# HBridges.net
KiCad netlist of a schematic drawn in Altium Designer
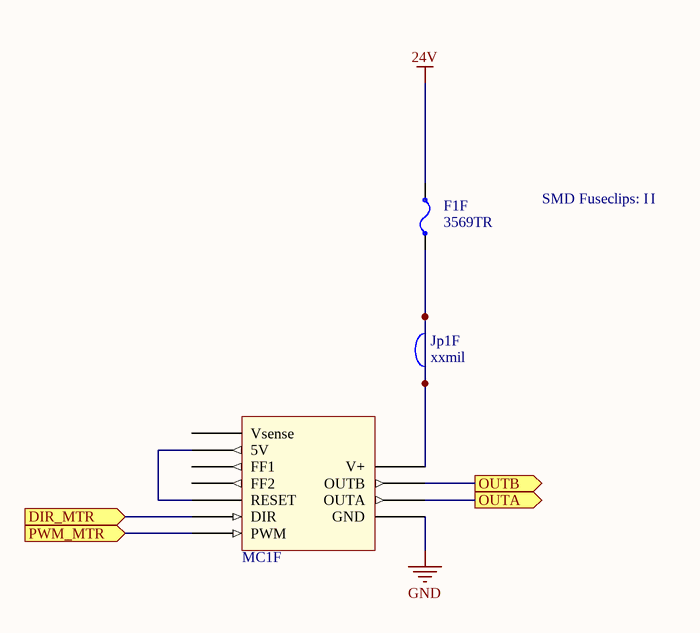
[diagram p0: HBridges.SchDoc]

(export (version "E")
  (design (tool "Eeschema 10.0.6"))
  (components
    (comp (ref "F1F")
      (value "3569TR")
      (footprint "Horizontal SMD fuse clip")
      (description "Fuse Clip Assembly")
      (fields (field (name "MANUFACTURER PART NUMBER") "3569TR"))
      (libsource (lib "Keystone SchLib") (part "3569TR"))
    )
    (comp (ref "i10F")
      (value "3569TR (Placeholder)")
      (description "Fuse Clip")
      (fields (field (name "MANUFACTURER PART NUMBER") "3569TR"))
      (libsource (lib "Keystone SchLib") (part "3569TR (Placeholder)"))
    )
    (comp (ref "i11F")
      (value "3569TR (Placeholder)")
      (description "Fuse Clip")
      (fields (field (name "MANUFACTURER PART NUMBER") "3569TR"))
      (libsource (lib "") (part "3569TR (Placeholder)_1"))
    )
    (comp (ref "Jp1F")
      (value "xxmil")
      (footprint "Jumper, 12AWG, 0.6\"")
      (description "Resistor")
      (fields (field (name "Comment") "Jumper"))
      (libsource (lib "URC") (part "Jump"))
    )
    (comp (ref "MC1F")
      (value "Motor Controller")
      (footprint "Pololu 24v12")
      (description "Pololu 24v12 Motor Driver")
      (libsource (lib "URC_Lib") (part "Pololu 24v12"))
    )
  )
  (nets
    (net (code "1") (name "/DIR_MTR") (class "Default")
      (node (ref "MC1F") (pin "DIR") (pinfunction "DIR_DIR") (pintype "input"))
    )
    (net (code "2") (name "/OUTA") (class "Default")
      (node (ref "MC1F") (pin "OUTA") (pinfunction "OUTA_OUTA") (pintype "output"))
    )
    (net (code "3") (name "/OUTB") (class "Default")
      (node (ref "MC1F") (pin "OUTB") (pinfunction "OUTB_OUTB") (pintype "output"))
    )
    (net (code "4") (name "/PWM_MTR") (class "Default")
      (node (ref "MC1F") (pin "PWM") (pinfunction "PWM_PWM") (pintype "input"))
    )
    (net (code "5") (name "24V") (class "Default")
      (node (ref "F1F") (pin "1") (pinfunction "1_1") (pintype "passive"))
    )
    (net (code "6") (name "GND") (class "Default")
      (node (ref "MC1F") (pin "GND") (pinfunction "GND_GND") (pintype "power_in"))
    )
    (net (code "7") (name "Net-(F1F-Pad2)") (class "Default")
      (node (ref "F1F") (pin "2") (pinfunction "2_2") (pintype "passive"))
      (node (ref "Jp1F") (pin "1") (pinfunction "1_1") (pintype "passive"))
      (node (ref "Jp1F") (pin "2") (pinfunction "2_2") (pintype "passive"))
      (node (ref "MC1F") (pin "V+") (pinfunction "V+_V+") (pintype "power_in"))
    )
    (net (code "8") (name "Net-(MC1F-Pad5V)") (class "Default")
      (node (ref "MC1F") (pin "5V") (pinfunction "5V_5V") (pintype "output"))
      (node (ref "MC1F") (pin "RESET") (pinfunction "RESET_RESET") (pintype "passive"))
    )
    (net (code "9") (name "unconnected-(MC1F-PadFF1)") (class "Default")
      (node (ref "MC1F") (pin "FF1") (pinfunction "FF1_FF1") (pintype "output"))
    )
    (net (code "10") (name "unconnected-(MC1F-PadFF2)") (class "Default")
      (node (ref "MC1F") (pin "FF2") (pinfunction "FF2_FF2") (pintype "output"))
    )
    (net (code "11") (name "unconnected-(MC1F-Vsense-PadV+_SENSE)") (class "Default")
      (node (ref "MC1F") (pin "V+_SENSE") (pinfunction "Vsense_V+_SENSE") (pintype "passive"))
    )
  )
)
